# VGAX_board_rev_17_for_JCL.net
KiCad netlist of a schematic drawn in EAGLE
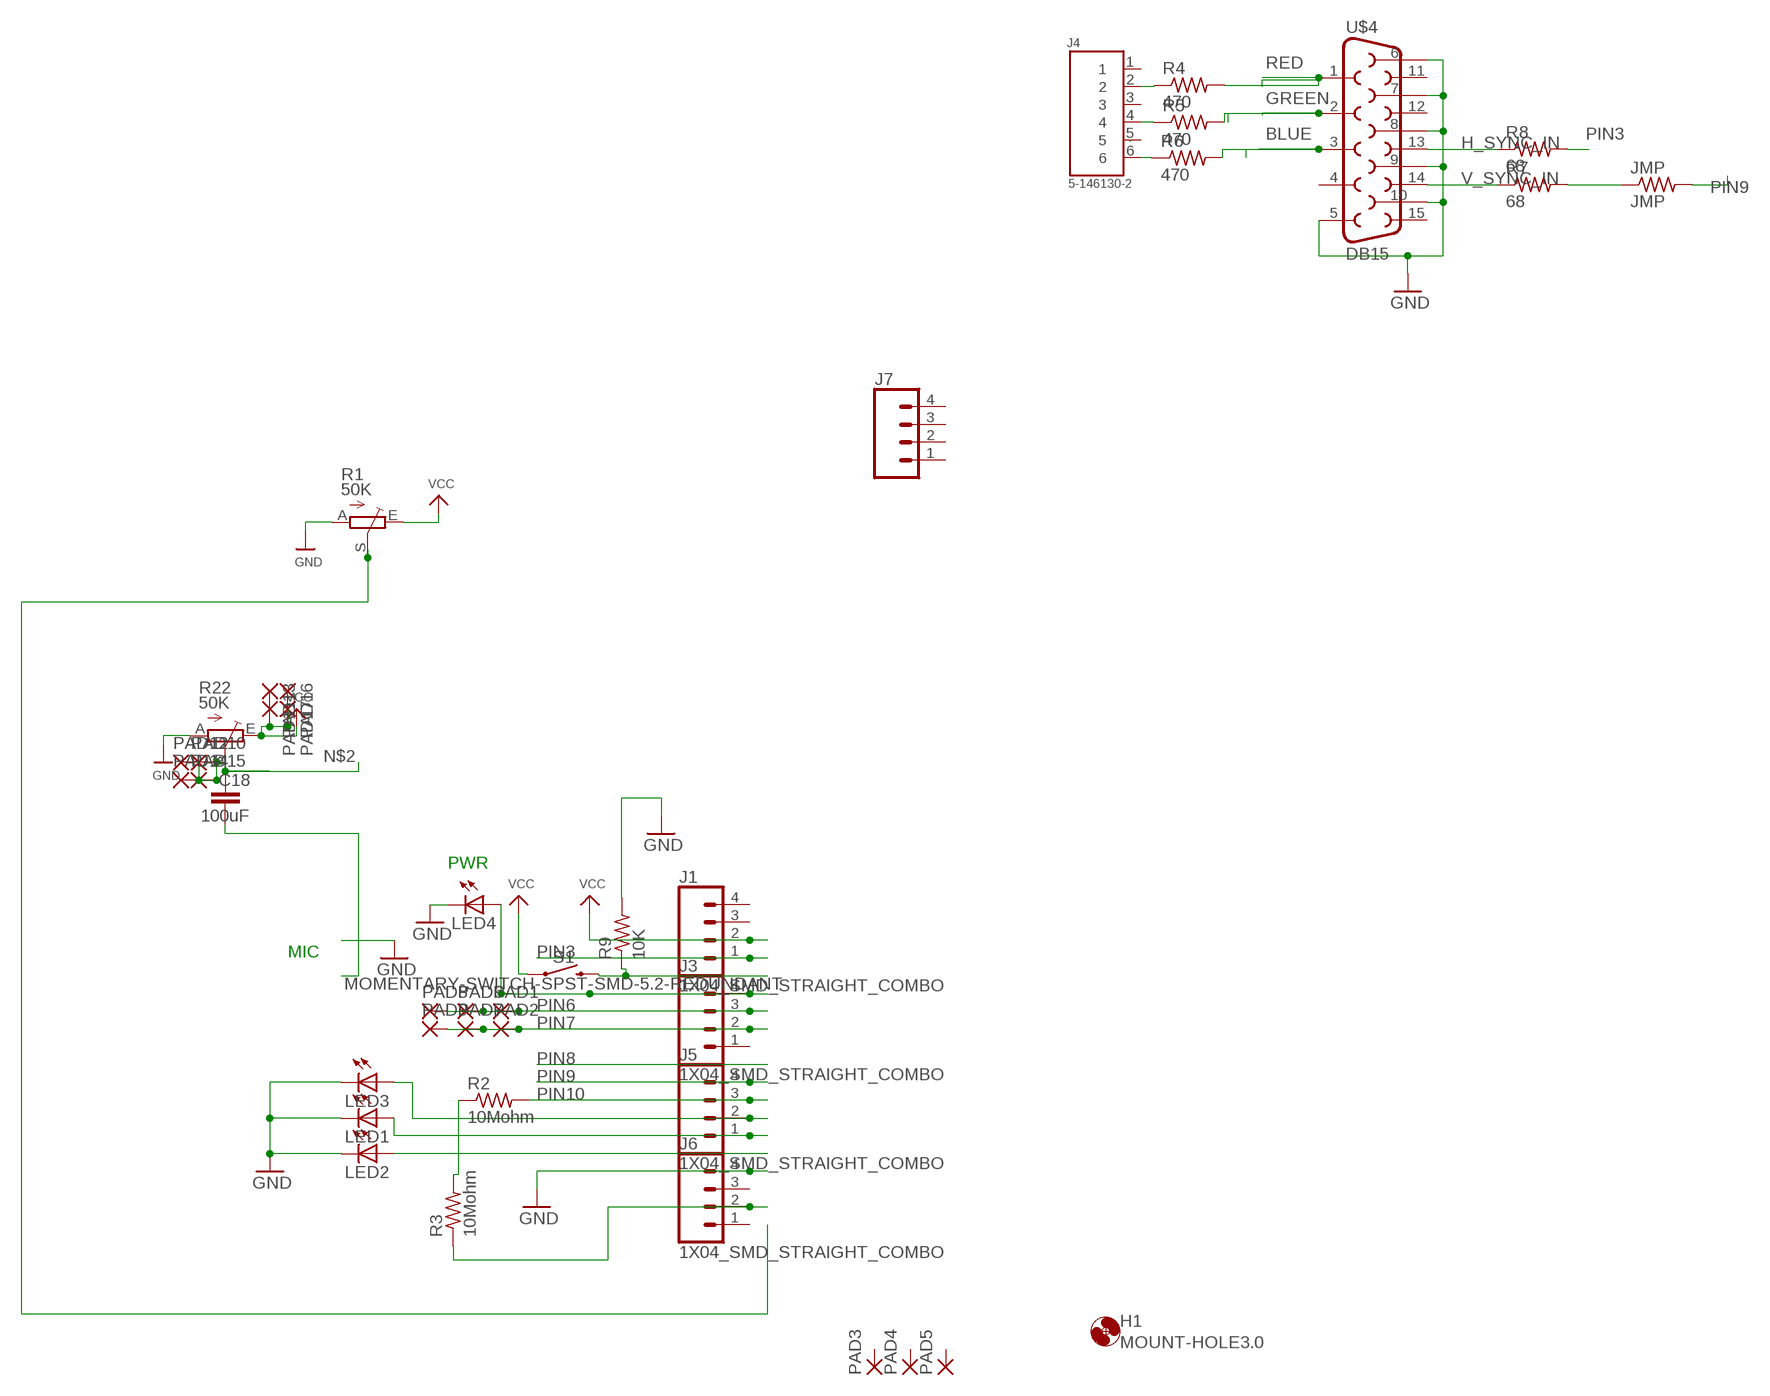
[diagram p0: schematic, sheet 1]

(export (version "E")
  (design (tool "Eeschema 10.0.6"))
  (components
    (comp (ref "C18")
      (value "100uF")
      (footprint "eagle-import:1206")
      (libsource (lib "eagle-import") (part "1.0UF-1206-50V-10%"))
    )
    (comp (ref "H1")
      (value "MOUNT-HOLE3.0")
      (footprint "eagle-import:3,0")
      (libsource (lib "eagle-import") (part "MOUNT-HOLE3.0"))
    )
    (comp (ref "J1")
      (value "1X04_SMD_STRAIGHT_COMBO")
      (footprint "eagle-import:1X04_SMD_VERTICAL_COMBO")
      (libsource (lib "eagle-import") (part "CONN_04SMD_STRAIGHT_COMBO"))
    )
    (comp (ref "J3")
      (value "1X04_SMD_STRAIGHT_COMBO")
      (footprint "eagle-import:1X04_SMD_VERTICAL_COMBO")
      (libsource (lib "eagle-import") (part "CONN_04SMD_STRAIGHT_COMBO"))
    )
    (comp (ref "J4")
      (value "5-146130-2")
      (footprint "eagle-import:5-146130-2")
      (fields
        (field (name "DIGIKEY_PART_NUMBER") "5-146130-2-ND")
        (field (name "MANUFACTURER") "TE Connectivity AMP Connectors")
        (field (name "CREATED_BY") "PCBLayout.com")
      )
      (libsource (lib "eagle-import") (part "5-146130-2"))
    )
    (comp (ref "J5")
      (value "1X04_SMD_STRAIGHT_COMBO")
      (footprint "eagle-import:1X04_SMD_VERTICAL_COMBO")
      (libsource (lib "eagle-import") (part "CONN_04SMD_STRAIGHT_COMBO"))
    )
    (comp (ref "J6")
      (value "1X04_SMD_STRAIGHT_COMBO")
      (footprint "eagle-import:1X04_SMD_VERTICAL_COMBO")
      (libsource (lib "eagle-import") (part "CONN_04SMD_STRAIGHT_COMBO"))
    )
    (comp (ref "J7")
      (value "1X04_SMD_STRAIGHT_COMBO")
      (footprint "eagle-import:1X04_SMD_VERTICAL_COMBO")
      (libsource (lib "eagle-import") (part "CONN_04SMD_STRAIGHT_COMBO"))
    )
    (comp (ref "JMP")
      (value "JMP")
      (footprint "eagle-import:M1206")
      (libsource (lib "eagle-import") (part "R-US_M1206"))
    )
    (comp (ref "LED1")
      (value "LEDCHIPLED_1206")
      (footprint "eagle-import:CHIPLED_1206")
      (libsource (lib "eagle-import") (part "LEDCHIPLED_1206"))
    )
    (comp (ref "LED2")
      (value "LEDCHIPLED_1206")
      (footprint "eagle-import:CHIPLED_1206")
      (libsource (lib "eagle-import") (part "LEDCHIPLED_1206"))
    )
    (comp (ref "LED3")
      (value "LEDCHIPLED_1206")
      (footprint "eagle-import:CHIPLED_1206")
      (libsource (lib "eagle-import") (part "LEDCHIPLED_1206"))
    )
    (comp (ref "LED4")
      (value "LEDCHIPLED_1206")
      (footprint "eagle-import:CHIPLED_1206")
      (libsource (lib "eagle-import") (part "LEDCHIPLED_1206"))
    )
    (comp (ref "PAD1")
      (value "SMD2")
      (footprint "eagle-import:SMD1,27-2,54")
      (libsource (lib "eagle-import") (part "SMD2"))
    )
    (comp (ref "PAD2")
      (value "SMD2")
      (footprint "eagle-import:SMD1,27-2,54")
      (libsource (lib "eagle-import") (part "SMD2"))
    )
    (comp (ref "PAD3")
      (value "SMD2")
      (footprint "eagle-import:SMD1,27-2,54")
      (libsource (lib "eagle-import") (part "SMD2"))
    )
    (comp (ref "PAD4")
      (value "SMD2")
      (footprint "eagle-import:SMD1,27-2,54")
      (libsource (lib "eagle-import") (part "SMD2"))
    )
    (comp (ref "PAD5")
      (value "SMD2")
      (footprint "eagle-import:SMD1,27-2,54")
      (libsource (lib "eagle-import") (part "SMD2"))
    )
    (comp (ref "PAD6")
      (value "SMD2")
      (footprint "eagle-import:SMD1,27-2,54")
      (libsource (lib "eagle-import") (part "SMD2"))
    )
    (comp (ref "PAD7")
      (value "SMD2")
      (footprint "eagle-import:SMD1,27-2,54")
      (libsource (lib "eagle-import") (part "SMD2"))
    )
    (comp (ref "PAD8")
      (value "SMD2")
      (footprint "eagle-import:SMD1,27-2,54")
      (libsource (lib "eagle-import") (part "SMD2"))
    )
    (comp (ref "PAD9")
      (value "SMD2")
      (footprint "eagle-import:SMD1,27-2,54")
      (libsource (lib "eagle-import") (part "SMD2"))
    )
    (comp (ref "PAD10")
      (value "SMD2")
      (footprint "eagle-import:SMD1,27-2,54")
      (libsource (lib "eagle-import") (part "SMD2"))
    )
    (comp (ref "PAD11")
      (value "SMD2")
      (footprint "eagle-import:SMD1,27-2,54")
      (libsource (lib "eagle-import") (part "SMD2"))
    )
    (comp (ref "PAD12")
      (value "SMD2")
      (footprint "eagle-import:SMD1,27-2,54")
      (libsource (lib "eagle-import") (part "SMD2"))
    )
    (comp (ref "PAD13")
      (value "SMD2")
      (footprint "eagle-import:SMD1,27-2,54")
      (libsource (lib "eagle-import") (part "SMD2"))
    )
    (comp (ref "PAD14")
      (value "SMD2")
      (footprint "eagle-import:SMD1,27-2,54")
      (libsource (lib "eagle-import") (part "SMD2"))
    )
    (comp (ref "PAD15")
      (value "SMD2")
      (footprint "eagle-import:SMD1,27-2,54")
      (libsource (lib "eagle-import") (part "SMD2"))
    )
    (comp (ref "PAD16")
      (value "SMD2")
      (footprint "eagle-import:SMD1,27-2,54")
      (libsource (lib "eagle-import") (part "SMD2"))
    )
    (comp (ref "PAD17")
      (value "SMD2")
      (footprint "eagle-import:SMD1,27-2,54")
      (libsource (lib "eagle-import") (part "SMD2"))
    )
    (comp (ref "R1")
      (value "50K")
      (footprint "eagle-import:CA9V")
      (libsource (lib "eagle-import") (part "TRIM_EU-CA9V"))
    )
    (comp (ref "R2")
      (value "10Mohm")
      (footprint "eagle-import:M1206")
      (libsource (lib "eagle-import") (part "R-US_M1206"))
    )
    (comp (ref "R3")
      (value "10Mohm")
      (footprint "eagle-import:M1206")
      (libsource (lib "eagle-import") (part "R-US_M1206"))
    )
    (comp (ref "R4")
      (value "470")
      (footprint "eagle-import:M1206")
      (libsource (lib "eagle-import") (part "R-US_M1206"))
    )
    (comp (ref "R5")
      (value "470")
      (footprint "eagle-import:M1206")
      (libsource (lib "eagle-import") (part "R-US_M1206"))
    )
    (comp (ref "R6")
      (value "470")
      (footprint "eagle-import:M1206")
      (libsource (lib "eagle-import") (part "R-US_M1206"))
    )
    (comp (ref "R7")
      (value "68")
      (footprint "eagle-import:M1206")
      (libsource (lib "eagle-import") (part "R-US_M1206"))
    )
    (comp (ref "R8")
      (value "68")
      (footprint "eagle-import:M1206")
      (libsource (lib "eagle-import") (part "R-US_M1206"))
    )
    (comp (ref "R9")
      (value "10K")
      (footprint "eagle-import:M1206")
      (libsource (lib "eagle-import") (part "R-US_M1206"))
    )
    (comp (ref "R22")
      (value "50K")
      (footprint "eagle-import:CA9V")
      (libsource (lib "eagle-import") (part "TRIM_EU-CA9V"))
    )
    (comp (ref "S1")
      (value "MOMENTARY-SWITCH-SPST-SMD-5.2-REDUNDANT")
      (footprint "eagle-import:TACTILE_SWITCH_SMD_5.2MM")
      (libsource (lib "eagle-import") (part "MOMENTARY-SWITCH-SPST-SMD-5.2-REDUNDANT"))
    )
    (comp (ref "U$4")
      (value "DB15")
      (footprint "eagle-import:DB15")
      (libsource (lib "eagle-import") (part "DB15"))
    )
  )
  (nets
    (net (code "1") (name "/BLUE") (class "Default")
      (node (ref "R6") (pin "2") (pinfunction "2_2") (pintype "passive"))
      (node (ref "U$4") (pin "3") (pinfunction "3_3") (pintype "passive"))
    )
    (net (code "2") (name "/GREEN") (class "Default")
      (node (ref "R5") (pin "2") (pinfunction "2_2") (pintype "passive"))
      (node (ref "U$4") (pin "2") (pinfunction "2_2") (pintype "passive"))
    )
    (net (code "3") (name "/H_SYNC_IN") (class "Default")
      (node (ref "R8") (pin "1") (pinfunction "1_1") (pintype "passive"))
      (node (ref "U$4") (pin "13") (pinfunction "13_13") (pintype "passive"))
    )
    (net (code "4") (name "/N$2") (class "Default")
      (node (ref "C18") (pin "1") (pinfunction "1_1") (pintype "passive"))
      (node (ref "PAD10") (pin "1") (pinfunction "P_1") (pintype "passive"))
      (node (ref "PAD12") (pin "1") (pinfunction "P_1") (pintype "passive"))
      (node (ref "PAD14") (pin "1") (pinfunction "P_1") (pintype "passive"))
      (node (ref "PAD15") (pin "1") (pinfunction "P_1") (pintype "passive"))
      (node (ref "R22") (pin "S") (pinfunction "S_S") (pintype "passive"))
    )
    (net (code "5") (name "/PIN3") (class "Default")
      (node (ref "J1") (pin "1") (pinfunction "1_1") (pintype "passive"))
      (node (ref "R8") (pin "2") (pinfunction "2_2") (pintype "passive"))
    )
    (net (code "6") (name "/PIN6") (class "Default")
      (node (ref "J3") (pin "3") (pinfunction "3_3") (pintype "passive"))
      (node (ref "PAD1") (pin "1") (pinfunction "P_1") (pintype "passive"))
      (node (ref "PAD6") (pin "1") (pinfunction "P_1") (pintype "passive"))
      (node (ref "PAD8") (pin "1") (pinfunction "P_1") (pintype "passive"))
    )
    (net (code "7") (name "/PIN7") (class "Default")
      (node (ref "J3") (pin "2") (pinfunction "2_2") (pintype "passive"))
      (node (ref "PAD2") (pin "1") (pinfunction "P_1") (pintype "passive"))
      (node (ref "PAD7") (pin "1") (pinfunction "P_1") (pintype "passive"))
      (node (ref "PAD9") (pin "1") (pinfunction "P_1") (pintype "passive"))
    )
    (net (code "8") (name "/PIN8") (class "Default")
      (node (ref "J6") (pin "2") (pinfunction "2_2") (pintype "passive"))
      (node (ref "R3") (pin "1") (pinfunction "1_1") (pintype "passive"))
    )
    (net (code "9") (name "/PIN9") (class "Default")
      (node (ref "J5") (pin "4") (pinfunction "4_4") (pintype "passive"))
      (node (ref "JMP") (pin "2") (pinfunction "2_2") (pintype "passive"))
    )
    (net (code "10") (name "/PIN10") (class "Default")
      (node (ref "J5") (pin "3") (pinfunction "3_3") (pintype "passive"))
      (node (ref "R2") (pin "2") (pinfunction "2_2") (pintype "passive"))
    )
    (net (code "11") (name "/RED") (class "Default")
      (node (ref "R4") (pin "2") (pinfunction "2_2") (pintype "passive"))
      (node (ref "U$4") (pin "1") (pinfunction "1_1") (pintype "passive"))
    )
    (net (code "12") (name "/V_SYNC_IN") (class "Default")
      (node (ref "R7") (pin "1") (pinfunction "1_1") (pintype "passive"))
      (node (ref "U$4") (pin "14") (pinfunction "14_14") (pintype "passive"))
    )
    (net (code "13") (name "GND") (class "Default")
      (node (ref "J6") (pin "4") (pinfunction "4_4") (pintype "passive"))
      (node (ref "LED1") (pin "C") (pinfunction "C_C") (pintype "passive"))
      (node (ref "LED2") (pin "C") (pinfunction "C_C") (pintype "passive"))
      (node (ref "LED3") (pin "C") (pinfunction "C_C") (pintype "passive"))
      (node (ref "LED4") (pin "C") (pinfunction "C_C") (pintype "passive"))
      (node (ref "R1") (pin "A") (pinfunction "A_A") (pintype "passive"))
      (node (ref "R22") (pin "A") (pinfunction "A_A") (pintype "passive"))
      (node (ref "R9") (pin "2") (pinfunction "2_2") (pintype "passive"))
      (node (ref "U$4") (pin "10") (pinfunction "10_10") (pintype "passive"))
      (node (ref "U$4") (pin "5") (pinfunction "5_5") (pintype "passive"))
      (node (ref "U$4") (pin "6") (pinfunction "6_6") (pintype "passive"))
      (node (ref "U$4") (pin "7") (pinfunction "7_7") (pintype "passive"))
      (node (ref "U$4") (pin "8") (pinfunction "8_8") (pintype "passive"))
      (node (ref "U$4") (pin "9") (pinfunction "9_9") (pintype "passive"))
    )
    (net (code "14") (name "Net-(J3-Pad4)") (class "Default")
      (node (ref "J3") (pin "4") (pinfunction "4_4") (pintype "passive"))
      (node (ref "LED4") (pin "A") (pinfunction "A_A") (pintype "passive"))
    )
    (net (code "15") (name "Net-(J4-Pad2)") (class "Default")
      (node (ref "J4") (pin "2") (pinfunction "2_2") (pintype "passive"))
      (node (ref "R4") (pin "1") (pinfunction "1_1") (pintype "passive"))
    )
    (net (code "16") (name "Net-(J4-Pad4)") (class "Default")
      (node (ref "J4") (pin "4") (pinfunction "4_4") (pintype "passive"))
      (node (ref "R5") (pin "1") (pinfunction "1_1") (pintype "passive"))
    )
    (net (code "17") (name "Net-(J4-Pad6)") (class "Default")
      (node (ref "J4") (pin "6") (pinfunction "6_6") (pintype "passive"))
      (node (ref "R6") (pin "1") (pinfunction "1_1") (pintype "passive"))
    )
    (net (code "18") (name "Net-(J5-Pad1)") (class "Default")
      (node (ref "J5") (pin "1") (pinfunction "1_1") (pintype "passive"))
      (node (ref "LED1") (pin "A") (pinfunction "A_A") (pintype "passive"))
    )
    (net (code "19") (name "Net-(J5-Pad2)") (class "Default")
      (node (ref "J5") (pin "2") (pinfunction "2_2") (pintype "passive"))
      (node (ref "LED3") (pin "A") (pinfunction "A_A") (pintype "passive"))
    )
    (net (code "20") (name "Net-(JMP-Pad1)") (class "Default")
      (node (ref "JMP") (pin "1") (pinfunction "1_1") (pintype "passive"))
      (node (ref "R7") (pin "2") (pinfunction "2_2") (pintype "passive"))
    )
    (net (code "21") (name "Net-(R2-Pad1)") (class "Default")
      (node (ref "R2") (pin "1") (pinfunction "1_1") (pintype "passive"))
      (node (ref "R3") (pin "2") (pinfunction "2_2") (pintype "passive"))
    )
    (net (code "22") (name "Net-(R9-Pad1)") (class "Default")
      (node (ref "R9") (pin "1") (pinfunction "1_1") (pintype "passive"))
      (node (ref "S1") (pin "3") (pinfunction "2_3") (pintype "passive"))
      (node (ref "S1") (pin "4") (pinfunction "2_4") (pintype "passive"))
    )
    (net (code "23") (name "VCC") (class "Default")
      (node (ref "J1") (pin "2") (pinfunction "2_2") (pintype "passive"))
      (node (ref "PAD11") (pin "1") (pinfunction "P_1") (pintype "passive"))
      (node (ref "PAD16") (pin "1") (pinfunction "P_1") (pintype "passive"))
      (node (ref "PAD17") (pin "1") (pinfunction "P_1") (pintype "passive"))
      (node (ref "R1") (pin "E") (pinfunction "E_E") (pintype "passive"))
      (node (ref "R22") (pin "E") (pinfunction "E_E") (pintype "passive"))
      (node (ref "S1") (pin "1") (pinfunction "1_1") (pintype "passive"))
      (node (ref "S1") (pin "2") (pinfunction "1_2") (pintype "passive"))
    )
    (net (code "24") (name "unconnected-(C18-Pad2)") (class "Default")
      (node (ref "C18") (pin "2") (pinfunction "2_2") (pintype "passive"))
    )
    (net (code "25") (name "unconnected-(J1-Pad3)") (class "Default")
      (node (ref "J1") (pin "3") (pinfunction "3_3") (pintype "passive"))
    )
    (net (code "26") (name "unconnected-(J1-Pad4)") (class "Default")
      (node (ref "J1") (pin "4") (pinfunction "4_4") (pintype "passive"))
    )
    (net (code "27") (name "unconnected-(J3-Pad1)") (class "Default")
      (node (ref "J3") (pin "1") (pinfunction "1_1") (pintype "passive"))
    )
    (net (code "28") (name "unconnected-(J4-Pad1)") (class "Default")
      (node (ref "J4") (pin "1") (pinfunction "1_1") (pintype "passive"))
    )
    (net (code "29") (name "unconnected-(J4-Pad3)") (class "Default")
      (node (ref "J4") (pin "3") (pinfunction "3_3") (pintype "passive"))
    )
    (net (code "30") (name "unconnected-(J4-Pad5)") (class "Default")
      (node (ref "J4") (pin "5") (pinfunction "5_5") (pintype "passive"))
    )
    (net (code "31") (name "unconnected-(J6-Pad1)") (class "Default")
      (node (ref "J6") (pin "1") (pinfunction "1_1") (pintype "passive"))
    )
    (net (code "32") (name "unconnected-(J6-Pad3)") (class "Default")
      (node (ref "J6") (pin "3") (pinfunction "3_3") (pintype "passive"))
    )
    (net (code "33") (name "unconnected-(J7-Pad1)") (class "Default")
      (node (ref "J7") (pin "1") (pinfunction "1_1") (pintype "passive"))
    )
    (net (code "34") (name "unconnected-(J7-Pad2)") (class "Default")
      (node (ref "J7") (pin "2") (pinfunction "2_2") (pintype "passive"))
    )
    (net (code "35") (name "unconnected-(J7-Pad3)") (class "Default")
      (node (ref "J7") (pin "3") (pinfunction "3_3") (pintype "passive"))
    )
    (net (code "36") (name "unconnected-(J7-Pad4)") (class "Default")
      (node (ref "J7") (pin "4") (pinfunction "4_4") (pintype "passive"))
    )
    (net (code "37") (name "unconnected-(LED2-PadA)") (class "Default")
      (node (ref "LED2") (pin "A") (pinfunction "A_A") (pintype "passive"))
    )
    (net (code "38") (name "unconnected-(PAD3-P-Pad1)") (class "Default")
      (node (ref "PAD3") (pin "1") (pinfunction "P_1") (pintype "passive"))
    )
    (net (code "39") (name "unconnected-(PAD4-P-Pad1)") (class "Default")
      (node (ref "PAD4") (pin "1") (pinfunction "P_1") (pintype "passive"))
    )
    (net (code "40") (name "unconnected-(PAD5-P-Pad1)") (class "Default")
      (node (ref "PAD5") (pin "1") (pinfunction "P_1") (pintype "passive"))
    )
    (net (code "41") (name "unconnected-(PAD13-P-Pad1)") (class "Default")
      (node (ref "PAD13") (pin "1") (pinfunction "P_1") (pintype "passive"))
    )
    (net (code "42") (name "unconnected-(R1-PadS)") (class "Default")
      (node (ref "R1") (pin "S") (pinfunction "S_S") (pintype "passive"))
    )
    (net (code "43") (name "unconnected-(U$4-Pad4)") (class "Default")
      (node (ref "U$4") (pin "4") (pinfunction "4_4") (pintype "passive"))
    )
    (net (code "44") (name "unconnected-(U$4-Pad11)") (class "Default")
      (node (ref "U$4") (pin "11") (pinfunction "11_11") (pintype "passive"))
    )
    (net (code "45") (name "unconnected-(U$4-Pad12)") (class "Default")
      (node (ref "U$4") (pin "12") (pinfunction "12_12") (pintype "passive"))
    )
    (net (code "46") (name "unconnected-(U$4-Pad15)") (class "Default")
      (node (ref "U$4") (pin "15") (pinfunction "15_15") (pintype "passive"))
    )
  )
)
